# R001A.net
KiCad netlist of a schematic drawn in EAGLE
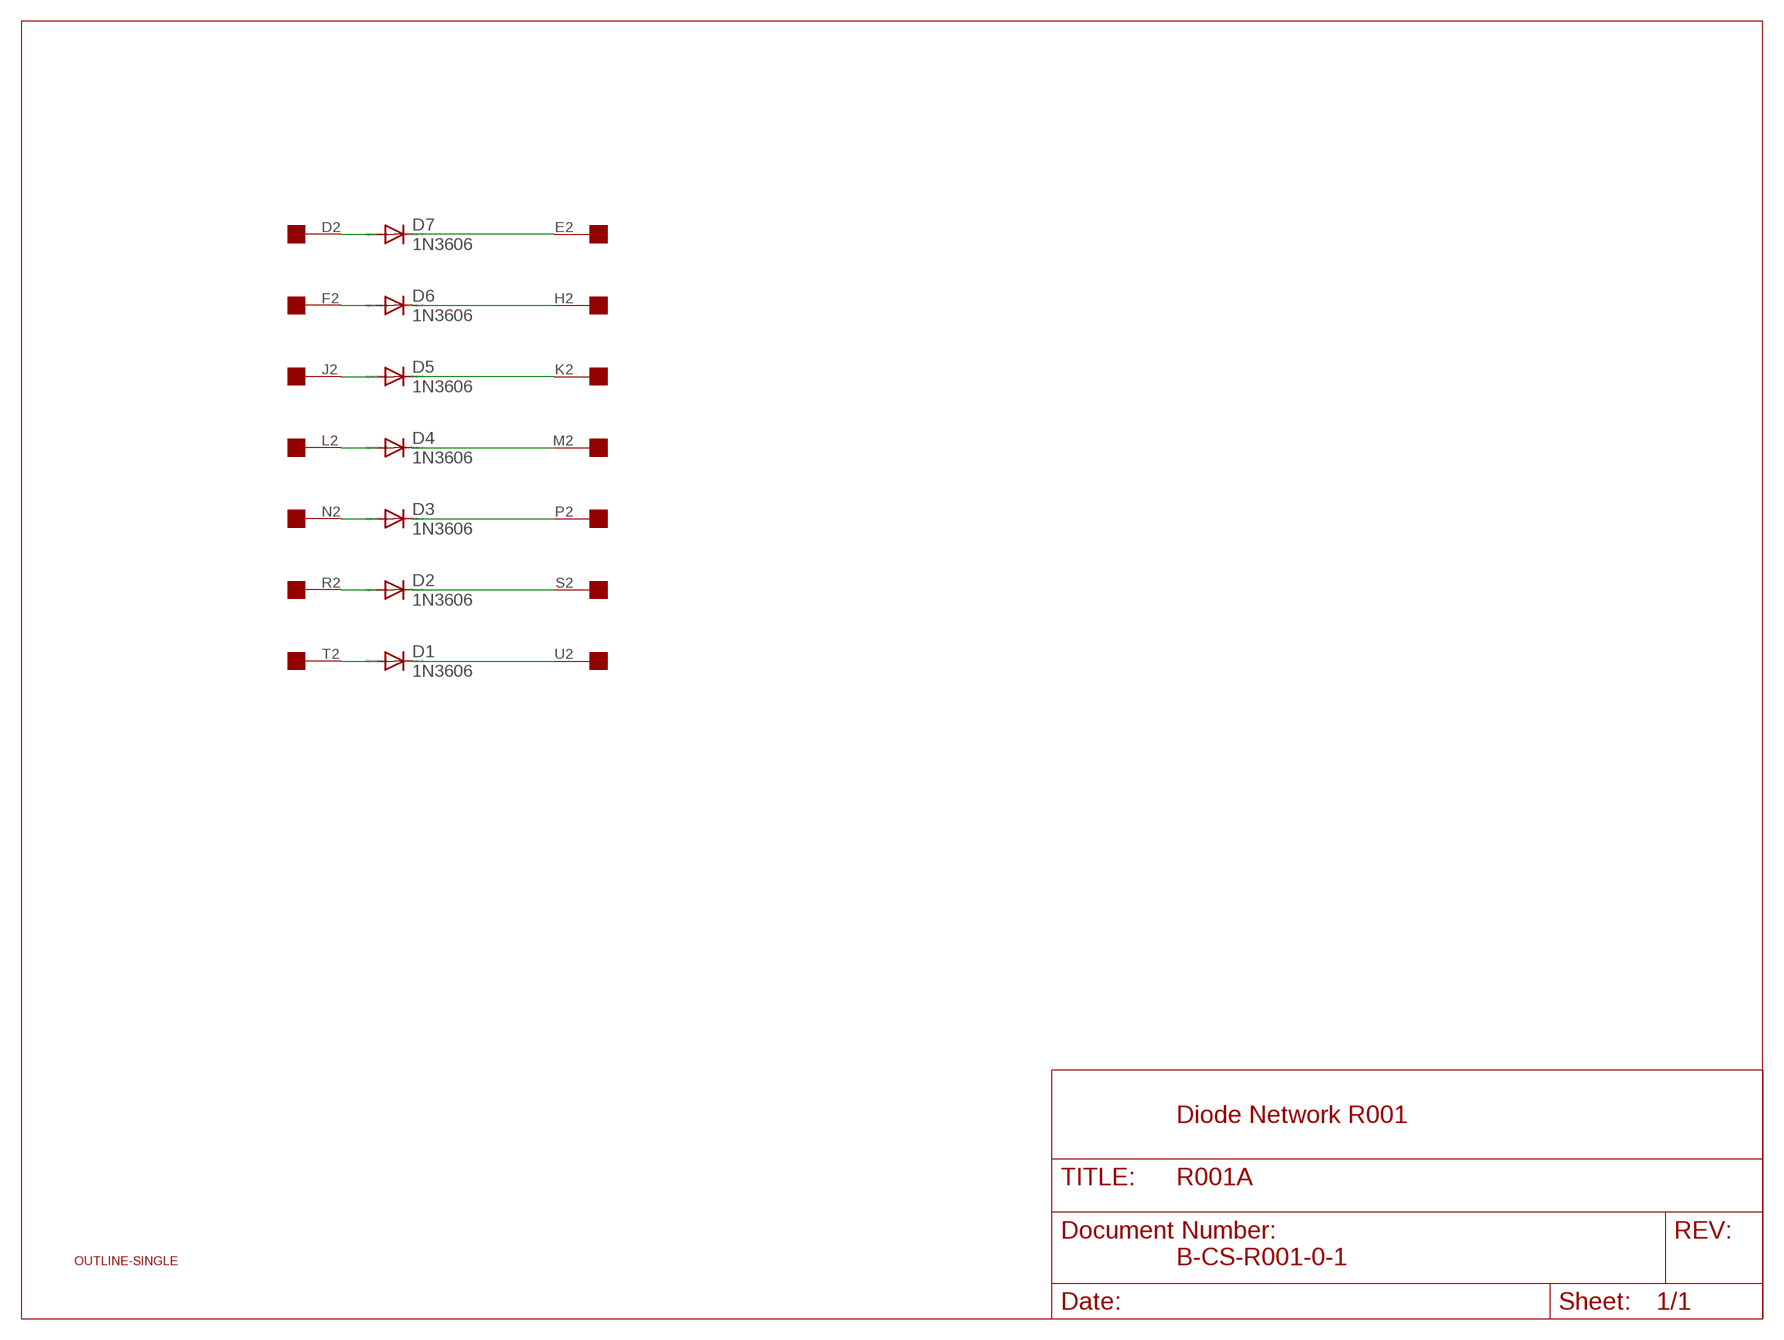
[diagram p0: schematic, sheet 1]

(export (version "E")
  (design (tool "Eeschema 10.0.6"))
  (components
    (comp (ref "D1")
      (value "1N3606")
      (footprint "eagle-import:DO35-10")
      (libsource (lib "eagle-import") (part "1N4148DO35-10"))
    )
    (comp (ref "D2")
      (value "1N3606")
      (footprint "eagle-import:DO35-10")
      (libsource (lib "eagle-import") (part "1N4148DO35-10"))
    )
    (comp (ref "D3")
      (value "1N3606")
      (footprint "eagle-import:DO35-10")
      (libsource (lib "eagle-import") (part "1N4148DO35-10"))
    )
    (comp (ref "D4")
      (value "1N3606")
      (footprint "eagle-import:DO35-10")
      (libsource (lib "eagle-import") (part "1N4148DO35-10"))
    )
    (comp (ref "D5")
      (value "1N3606")
      (footprint "eagle-import:DO35-10")
      (libsource (lib "eagle-import") (part "1N4148DO35-10"))
    )
    (comp (ref "D6")
      (value "1N3606")
      (footprint "eagle-import:DO35-10")
      (libsource (lib "eagle-import") (part "1N4148DO35-10"))
    )
    (comp (ref "D7")
      (value "1N3606")
      (footprint "eagle-import:DO35-10")
      (libsource (lib "eagle-import") (part "1N4148DO35-10"))
    )
    (comp (ref "U$1")
      (value "OUTLINE-SINGLE")
      (footprint "eagle-import:SINGLE")
      (libsource (lib "eagle-import") (part "OUTLINE-SINGLE"))
    )
    (comp (ref "U$2")
      (value "EDGE-1")
      (footprint "eagle-import:EDGE-CON1")
      (libsource (lib "eagle-import") (part "EDGE-1"))
    )
  )
  (nets
    (net (code "1") (name "Net-(U$2D-1)") (class "Default")
      (node (ref "D7") (pin "A") (pinfunction "A_A") (pintype "passive"))
      (node (ref "U$2") (pin "D2") (pinfunction "1_D2") (pintype "bidirectional"))
    )
    (net (code "2") (name "Net-(U$2E-1)") (class "Default")
      (node (ref "D7") (pin "C") (pinfunction "C_C") (pintype "passive"))
      (node (ref "U$2") (pin "E2") (pinfunction "1_E2") (pintype "bidirectional"))
    )
    (net (code "3") (name "Net-(U$2F-1)") (class "Default")
      (node (ref "D6") (pin "A") (pinfunction "A_A") (pintype "passive"))
      (node (ref "U$2") (pin "F2") (pinfunction "1_F2") (pintype "bidirectional"))
    )
    (net (code "4") (name "Net-(U$2G-1)") (class "Default")
      (node (ref "D6") (pin "C") (pinfunction "C_C") (pintype "passive"))
      (node (ref "U$2") (pin "H2") (pinfunction "1_H2") (pintype "bidirectional"))
    )
    (net (code "5") (name "Net-(U$2H-1)") (class "Default")
      (node (ref "D5") (pin "A") (pinfunction "A_A") (pintype "passive"))
      (node (ref "U$2") (pin "J2") (pinfunction "1_J2") (pintype "bidirectional"))
    )
    (net (code "6") (name "Net-(U$2I-1)") (class "Default")
      (node (ref "D5") (pin "C") (pinfunction "C_C") (pintype "passive"))
      (node (ref "U$2") (pin "K2") (pinfunction "1_K2") (pintype "bidirectional"))
    )
    (net (code "7") (name "Net-(U$2J-1)") (class "Default")
      (node (ref "D4") (pin "A") (pinfunction "A_A") (pintype "passive"))
      (node (ref "U$2") (pin "L2") (pinfunction "1_L2") (pintype "bidirectional"))
    )
    (net (code "8") (name "Net-(U$2K-1)") (class "Default")
      (node (ref "D4") (pin "C") (pinfunction "C_C") (pintype "passive"))
      (node (ref "U$2") (pin "M2") (pinfunction "1_M2") (pintype "bidirectional"))
    )
    (net (code "9") (name "Net-(U$2L-1)") (class "Default")
      (node (ref "D3") (pin "A") (pinfunction "A_A") (pintype "passive"))
      (node (ref "U$2") (pin "N2") (pinfunction "1_N2") (pintype "bidirectional"))
    )
    (net (code "10") (name "Net-(U$2M-1)") (class "Default")
      (node (ref "D3") (pin "C") (pinfunction "C_C") (pintype "passive"))
      (node (ref "U$2") (pin "P2") (pinfunction "1_P2") (pintype "bidirectional"))
    )
    (net (code "11") (name "Net-(U$2N-1)") (class "Default")
      (node (ref "D2") (pin "A") (pinfunction "A_A") (pintype "passive"))
      (node (ref "U$2") (pin "R2") (pinfunction "1_R2") (pintype "bidirectional"))
    )
    (net (code "12") (name "Net-(U$2O-1)") (class "Default")
      (node (ref "D2") (pin "C") (pinfunction "C_C") (pintype "passive"))
      (node (ref "U$2") (pin "S2") (pinfunction "1_S2") (pintype "bidirectional"))
    )
    (net (code "13") (name "Net-(U$2P-1)") (class "Default")
      (node (ref "D1") (pin "A") (pinfunction "A_A") (pintype "passive"))
      (node (ref "U$2") (pin "T2") (pinfunction "1_T2") (pintype "bidirectional"))
    )
    (net (code "14") (name "Net-(U$2Q-1)") (class "Default")
      (node (ref "D1") (pin "C") (pinfunction "C_C") (pintype "passive"))
      (node (ref "U$2") (pin "U2") (pinfunction "1_U2") (pintype "bidirectional"))
    )
  )
)
